# PART2_PowerSupply.net
KiCad netlist of a schematic drawn in Altium Designer
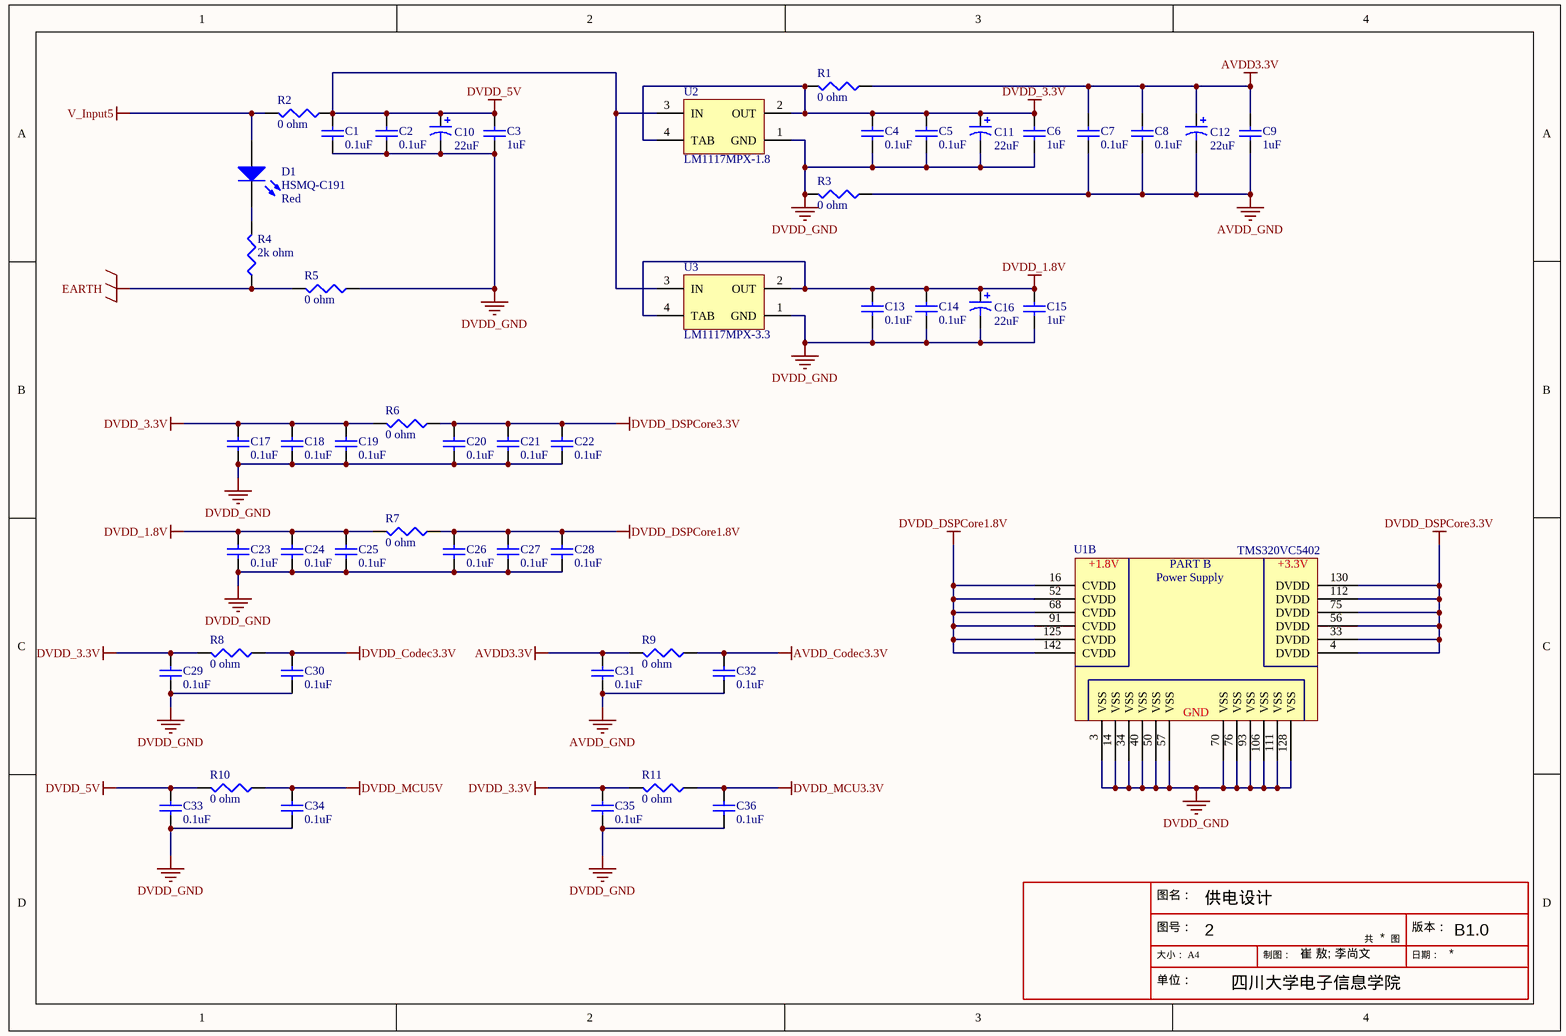
[diagram p0: PART2_PowerSupply.SchDoc]

(export (version "E")
  (design (tool "Eeschema 10.0.6"))
  (components
    (comp (ref "C1")
      (value "0.1uF")
      (footprint "1608[0603]")
      (description "贴片电容 1608")
      (fields (field (name "Comment") "Cap Semi") (field (name "PUBLISHER") "Altium Limited"))
      (libsource (lib "Miscellaneous Devices") (part "Cap Semi"))
    )
    (comp (ref "C2")
      (value "0.1uF")
      (footprint "1608[0603]")
      (description "贴片电容 1608")
      (fields (field (name "Comment") "Cap Semi") (field (name "PUBLISHER") "Altium Limited"))
      (libsource (lib "Miscellaneous Devices") (part "Cap Semi"))
    )
    (comp (ref "C3")
      (value "1uF")
      (footprint "1608[0603]")
      (description "贴片电容 1608")
      (fields (field (name "Comment") "Cap Semi") (field (name "PUBLISHER") "Altium Limited"))
      (libsource (lib "Miscellaneous Devices") (part "Cap Semi"))
    )
    (comp (ref "C4")
      (value "0.1uF")
      (footprint "1608[0603]")
      (description "贴片电容 1608")
      (fields (field (name "Comment") "Cap Semi") (field (name "PUBLISHER") "Altium Limited"))
      (libsource (lib "Miscellaneous Devices") (part "Cap Semi"))
    )
    (comp (ref "C5")
      (value "0.1uF")
      (footprint "1608[0603]")
      (description "贴片电容 1608")
      (fields (field (name "Comment") "Cap Semi") (field (name "PUBLISHER") "Altium Limited"))
      (libsource (lib "Miscellaneous Devices") (part "Cap Semi"))
    )
    (comp (ref "C6")
      (value "1uF")
      (footprint "1608[0603]")
      (description "贴片电容 1608")
      (fields (field (name "Comment") "Cap Semi") (field (name "PUBLISHER") "Altium Limited"))
      (libsource (lib "Miscellaneous Devices") (part "Cap Semi"))
    )
    (comp (ref "C7")
      (value "0.1uF")
      (footprint "1608[0603]")
      (description "贴片电容 1608")
      (fields (field (name "Comment") "Cap Semi") (field (name "PUBLISHER") "Altium Limited"))
      (libsource (lib "Miscellaneous Devices") (part "Cap Semi"))
    )
    (comp (ref "C8")
      (value "0.1uF")
      (footprint "1608[0603]")
      (description "贴片电容 1608")
      (fields (field (name "Comment") "Cap Semi") (field (name "PUBLISHER") "Altium Limited"))
      (libsource (lib "Miscellaneous Devices") (part "Cap Semi"))
    )
    (comp (ref "C9")
      (value "1uF")
      (footprint "1608[0603]")
      (description "贴片电容 1608")
      (fields (field (name "Comment") "Cap Semi") (field (name "PUBLISHER") "Altium Limited"))
      (libsource (lib "Miscellaneous Devices") (part "Cap Semi"))
    )
    (comp (ref "C10")
      (value "22uF")
      (footprint "C0805")
      (description "贴片钽电容 C0805")
      (fields (field (name "Comment") "Cap Tan") (field (name "PUBLISHER") "Altium Limited"))
      (libsource (lib "Miscellaneous Devices") (part "Cap Pol3"))
    )
    (comp (ref "C11")
      (value "22uF")
      (footprint "C0805")
      (description "贴片钽电容 C0805")
      (fields (field (name "Comment") "Cap Tan") (field (name "PUBLISHER") "Altium Limited"))
      (libsource (lib "Miscellaneous Devices") (part "Cap Pol3"))
    )
    (comp (ref "C12")
      (value "22uF")
      (footprint "C0805")
      (description "贴片钽电容 C0805")
      (fields (field (name "Comment") "Cap Tan") (field (name "PUBLISHER") "Altium Limited"))
      (libsource (lib "Miscellaneous Devices") (part "Cap Pol3"))
    )
    (comp (ref "C13")
      (value "0.1uF")
      (footprint "1608[0603]")
      (description "贴片电容 1608")
      (fields (field (name "Comment") "Cap Semi") (field (name "PUBLISHER") "Altium Limited"))
      (libsource (lib "Miscellaneous Devices") (part "Cap Semi"))
    )
    (comp (ref "C14")
      (value "0.1uF")
      (footprint "1608[0603]")
      (description "贴片电容 1608")
      (fields (field (name "Comment") "Cap Semi") (field (name "PUBLISHER") "Altium Limited"))
      (libsource (lib "Miscellaneous Devices") (part "Cap Semi"))
    )
    (comp (ref "C15")
      (value "1uF")
      (footprint "1608[0603]")
      (description "贴片电容 1608")
      (fields (field (name "Comment") "Cap Semi") (field (name "PUBLISHER") "Altium Limited"))
      (libsource (lib "Miscellaneous Devices") (part "Cap Semi"))
    )
    (comp (ref "C16")
      (value "22uF")
      (footprint "C0805")
      (description "贴片钽电容 C0805")
      (fields (field (name "Comment") "Cap Tan") (field (name "PUBLISHER") "Altium Limited"))
      (libsource (lib "Miscellaneous Devices") (part "Cap Pol3"))
    )
    (comp (ref "C17")
      (value "0.1uF")
      (footprint "1608[0603]")
      (description "贴片电容 1608")
      (fields (field (name "Comment") "Cap Semi") (field (name "PUBLISHER") "Altium Limited"))
      (libsource (lib "Miscellaneous Devices") (part "Cap Semi"))
    )
    (comp (ref "C18")
      (value "0.1uF")
      (footprint "1608[0603]")
      (description "贴片电容 1608")
      (fields (field (name "Comment") "Cap Semi") (field (name "PUBLISHER") "Altium Limited"))
      (libsource (lib "Miscellaneous Devices") (part "Cap Semi"))
    )
    (comp (ref "C19")
      (value "0.1uF")
      (footprint "1608[0603]")
      (description "贴片电容 1608")
      (fields (field (name "Comment") "Cap Semi") (field (name "PUBLISHER") "Altium Limited"))
      (libsource (lib "Miscellaneous Devices") (part "Cap Semi"))
    )
    (comp (ref "C20")
      (value "0.1uF")
      (footprint "1608[0603]")
      (description "贴片电容 1608")
      (fields (field (name "Comment") "Cap Semi") (field (name "PUBLISHER") "Altium Limited"))
      (libsource (lib "Miscellaneous Devices") (part "Cap Semi"))
    )
    (comp (ref "C21")
      (value "0.1uF")
      (footprint "1608[0603]")
      (description "贴片电容 1608")
      (fields (field (name "Comment") "Cap Semi") (field (name "PUBLISHER") "Altium Limited"))
      (libsource (lib "Miscellaneous Devices") (part "Cap Semi"))
    )
    (comp (ref "C22")
      (value "0.1uF")
      (footprint "1608[0603]")
      (description "贴片电容 1608")
      (fields (field (name "Comment") "Cap Semi") (field (name "PUBLISHER") "Altium Limited"))
      (libsource (lib "Miscellaneous Devices") (part "Cap Semi"))
    )
    (comp (ref "C23")
      (value "0.1uF")
      (footprint "1608[0603]")
      (description "贴片电容 1608")
      (fields (field (name "Comment") "Cap Semi") (field (name "PUBLISHER") "Altium Limited"))
      (libsource (lib "Miscellaneous Devices") (part "Cap Semi"))
    )
    (comp (ref "C24")
      (value "0.1uF")
      (footprint "1608[0603]")
      (description "贴片电容 1608")
      (fields (field (name "Comment") "Cap Semi") (field (name "PUBLISHER") "Altium Limited"))
      (libsource (lib "Miscellaneous Devices") (part "Cap Semi"))
    )
    (comp (ref "C25")
      (value "0.1uF")
      (footprint "1608[0603]")
      (description "贴片电容 1608")
      (fields (field (name "Comment") "Cap Semi") (field (name "PUBLISHER") "Altium Limited"))
      (libsource (lib "Miscellaneous Devices") (part "Cap Semi"))
    )
    (comp (ref "C26")
      (value "0.1uF")
      (footprint "1608[0603]")
      (description "贴片电容 1608")
      (fields (field (name "Comment") "Cap Semi") (field (name "PUBLISHER") "Altium Limited"))
      (libsource (lib "Miscellaneous Devices") (part "Cap Semi"))
    )
    (comp (ref "C27")
      (value "0.1uF")
      (footprint "1608[0603]")
      (description "贴片电容 1608")
      (fields (field (name "Comment") "Cap Semi") (field (name "PUBLISHER") "Altium Limited"))
      (libsource (lib "Miscellaneous Devices") (part "Cap Semi"))
    )
    (comp (ref "C28")
      (value "0.1uF")
      (footprint "1608[0603]")
      (description "贴片电容 1608")
      (fields (field (name "Comment") "Cap Semi") (field (name "PUBLISHER") "Altium Limited"))
      (libsource (lib "Miscellaneous Devices") (part "Cap Semi"))
    )
    (comp (ref "C29")
      (value "0.1uF")
      (footprint "1608[0603]")
      (description "贴片电容 1608")
      (fields (field (name "Comment") "Cap Semi") (field (name "PUBLISHER") "Altium Limited"))
      (libsource (lib "Miscellaneous Devices") (part "Cap Semi"))
    )
    (comp (ref "C30")
      (value "0.1uF")
      (footprint "1608[0603]")
      (description "贴片电容 1608")
      (fields (field (name "Comment") "Cap Semi") (field (name "PUBLISHER") "Altium Limited"))
      (libsource (lib "Miscellaneous Devices") (part "Cap Semi"))
    )
    (comp (ref "C31")
      (value "0.1uF")
      (footprint "1608[0603]")
      (description "贴片电容 1608")
      (fields (field (name "Comment") "Cap Semi") (field (name "PUBLISHER") "Altium Limited"))
      (libsource (lib "Miscellaneous Devices") (part "Cap Semi"))
    )
    (comp (ref "C32")
      (value "0.1uF")
      (footprint "1608[0603]")
      (description "贴片电容 1608")
      (fields (field (name "Comment") "Cap Semi") (field (name "PUBLISHER") "Altium Limited"))
      (libsource (lib "Miscellaneous Devices") (part "Cap Semi"))
    )
    (comp (ref "C33")
      (value "0.1uF")
      (footprint "1608[0603]")
      (description "贴片电容 1608")
      (fields (field (name "Comment") "Cap Semi") (field (name "PUBLISHER") "Altium Limited"))
      (libsource (lib "Miscellaneous Devices") (part "Cap Semi"))
    )
    (comp (ref "C34")
      (value "0.1uF")
      (footprint "1608[0603]")
      (description "贴片电容 1608")
      (fields (field (name "Comment") "Cap Semi") (field (name "PUBLISHER") "Altium Limited"))
      (libsource (lib "Miscellaneous Devices") (part "Cap Semi"))
    )
    (comp (ref "C35")
      (value "0.1uF")
      (footprint "1608[0603]")
      (description "贴片电容 1608")
      (fields (field (name "Comment") "Cap Semi") (field (name "PUBLISHER") "Altium Limited"))
      (libsource (lib "Miscellaneous Devices") (part "Cap Semi"))
    )
    (comp (ref "C36")
      (value "0.1uF")
      (footprint "1608[0603]")
      (description "贴片电容 1608")
      (fields (field (name "Comment") "Cap Semi") (field (name "PUBLISHER") "Altium Limited"))
      (libsource (lib "Miscellaneous Devices") (part "Cap Semi"))
    )
    (comp (ref "D1")
      (value "HSMQ-C191")
      (footprint "1.6X0.8X0.6")
      (description "Top Mount Low Profile Chip LED, Green")
      (fields (field (name "LED_COLOUR") "Red") (field (name "PUBLISHER") "Altium Limited"))
      (libsource (lib "Agilent Optoelectronic LED") (part "HSMQ-C191"))
    )
    (comp (ref "R1")
      (value "0 ohm")
      (footprint "J1-0603")
      (description "贴片电阻 0603")
      (fields (field (name "Comment") "Res3") (field (name "PUBLISHER") "Altium Limited"))
      (libsource (lib "Miscellaneous Devices") (part "Res3"))
    )
    (comp (ref "R2")
      (value "0 ohm")
      (footprint "J1-0603")
      (description "贴片电阻 0603")
      (fields (field (name "Comment") "Res3") (field (name "PUBLISHER") "Altium Limited"))
      (libsource (lib "Miscellaneous Devices") (part "Res3"))
    )
    (comp (ref "R3")
      (value "0 ohm")
      (footprint "J1-0603")
      (description "贴片电阻 0603")
      (fields (field (name "Comment") "Res3") (field (name "PUBLISHER") "Altium Limited"))
      (libsource (lib "Miscellaneous Devices") (part "Res3"))
    )
    (comp (ref "R4")
      (value "2k ohm")
      (footprint "J1-0603")
      (description "贴片电阻 0603")
      (fields (field (name "Comment") "Res3") (field (name "PUBLISHER") "Altium Limited"))
      (libsource (lib "Miscellaneous Devices") (part "Res3"))
    )
    (comp (ref "R5")
      (value "0 ohm")
      (footprint "J1-0603")
      (description "贴片电阻 0603")
      (fields (field (name "Comment") "Res3") (field (name "PUBLISHER") "Altium Limited"))
      (libsource (lib "Miscellaneous Devices") (part "Res3"))
    )
    (comp (ref "R6")
      (value "0 ohm")
      (footprint "J1-0603")
      (description "贴片电阻 0603")
      (fields (field (name "Comment") "Res3") (field (name "PUBLISHER") "Altium Limited"))
      (libsource (lib "Miscellaneous Devices") (part "Res3"))
    )
    (comp (ref "R7")
      (value "0 ohm")
      (footprint "J1-0603")
      (description "贴片电阻 0603")
      (fields (field (name "Comment") "Res3") (field (name "PUBLISHER") "Altium Limited"))
      (libsource (lib "Miscellaneous Devices") (part "Res3"))
    )
    (comp (ref "R8")
      (value "0 ohm")
      (footprint "J1-0603")
      (description "贴片电阻 0603")
      (fields (field (name "Comment") "Res3") (field (name "PUBLISHER") "Altium Limited"))
      (libsource (lib "Miscellaneous Devices") (part "Res3"))
    )
    (comp (ref "R9")
      (value "0 ohm")
      (footprint "J1-0603")
      (description "贴片电阻 0603")
      (fields (field (name "Comment") "Res3") (field (name "PUBLISHER") "Altium Limited"))
      (libsource (lib "Miscellaneous Devices") (part "Res3"))
    )
    (comp (ref "R10")
      (value "0 ohm")
      (footprint "J1-0603")
      (description "贴片电阻 0603")
      (fields (field (name "Comment") "Res3") (field (name "PUBLISHER") "Altium Limited"))
      (libsource (lib "Miscellaneous Devices") (part "Res3"))
    )
    (comp (ref "R11")
      (value "0 ohm")
      (footprint "J1-0603")
      (description "贴片电阻 0603")
      (fields (field (name "Comment") "Res3") (field (name "PUBLISHER") "Altium Limited"))
      (libsource (lib "Miscellaneous Devices") (part "Res3"))
    )
    (comp (ref "U1")
      (value "TMS320VC5402")
      (footprint "TMS320VC5401_PQFP144")
      (libsource (lib "TMS320VC5401") (part "TMS320VC5402"))
    )
    (comp (ref "U2")
      (value "LM1117MPX-1.8")
      (footprint "MP04A_N")
      (description "800mA Low-Dropout Linear Regulator, 4-pin SOT-223")
      (fields
        (field (name "MANUFACTURER") "National Semiconductor")
        (field (name "PUBLISHER") "Altium Limited")
      )
      (libsource (lib "NSC LDO") (part "LM1117MPX-1.8"))
    )
    (comp (ref "U3")
      (value "LM1117MPX-3.3")
      (footprint "MP04A_N")
      (description "800mA Low-Dropout Linear Regulator, 4-pin SOT-223")
      (fields
        (field (name "MANUFACTURER") "National Semiconductor")
        (field (name "PUBLISHER") "Altium Limited")
      )
      (libsource (lib "NSC LDO") (part "LM1117MPX-3.3"))
    )
  )
  (nets
    (net (code "1") (name "AVDD3.3V") (class "Default")
      (node (ref "C12") (pin "1") (pinfunction "1_1") (pintype "passive"))
      (node (ref "C31") (pin "1") (pinfunction "1_1") (pintype "passive"))
      (node (ref "C7") (pin "1") (pinfunction "1_1") (pintype "passive"))
      (node (ref "C8") (pin "1") (pinfunction "1_1") (pintype "passive"))
      (node (ref "C9") (pin "1") (pinfunction "1_1") (pintype "passive"))
      (node (ref "R1") (pin "1") (pinfunction "1_1") (pintype "passive"))
      (node (ref "R9") (pin "2") (pinfunction "2_2") (pintype "passive"))
    )
    (net (code "2") (name "AVDD_Codec3.3V") (class "Default")
      (node (ref "C32") (pin "1") (pinfunction "1_1") (pintype "passive"))
      (node (ref "R9") (pin "1") (pinfunction "1_1") (pintype "passive"))
    )
    (net (code "3") (name "AVDD_GND") (class "Default")
      (node (ref "C12") (pin "2") (pinfunction "2_2") (pintype "passive"))
      (node (ref "C31") (pin "2") (pinfunction "2_2") (pintype "passive"))
      (node (ref "C32") (pin "2") (pinfunction "2_2") (pintype "passive"))
      (node (ref "C7") (pin "2") (pinfunction "2_2") (pintype "passive"))
      (node (ref "C8") (pin "2") (pinfunction "2_2") (pintype "passive"))
      (node (ref "C9") (pin "2") (pinfunction "2_2") (pintype "passive"))
      (node (ref "R3") (pin "1") (pinfunction "1_1") (pintype "passive"))
    )
    (net (code "4") (name "DVDD_1.8V") (class "Default")
      (node (ref "C13") (pin "1") (pinfunction "1_1") (pintype "passive"))
      (node (ref "C14") (pin "1") (pinfunction "1_1") (pintype "passive"))
      (node (ref "C15") (pin "1") (pinfunction "1_1") (pintype "passive"))
      (node (ref "C16") (pin "1") (pinfunction "1_1") (pintype "passive"))
      (node (ref "C23") (pin "1") (pinfunction "1_1") (pintype "passive"))
      (node (ref "C24") (pin "1") (pinfunction "1_1") (pintype "passive"))
      (node (ref "C25") (pin "1") (pinfunction "1_1") (pintype "passive"))
      (node (ref "R7") (pin "2") (pinfunction "2_2") (pintype "passive"))
      (node (ref "U3") (pin "2") (pinfunction "OUT_2") (pintype "power_in"))
      (node (ref "U3") (pin "4") (pinfunction "TAB_4") (pintype "power_in"))
    )
    (net (code "5") (name "DVDD_3.3V") (class "Default")
      (node (ref "C11") (pin "1") (pinfunction "1_1") (pintype "passive"))
      (node (ref "C17") (pin "1") (pinfunction "1_1") (pintype "passive"))
      (node (ref "C18") (pin "1") (pinfunction "1_1") (pintype "passive"))
      (node (ref "C19") (pin "1") (pinfunction "1_1") (pintype "passive"))
      (node (ref "C29") (pin "1") (pinfunction "1_1") (pintype "passive"))
      (node (ref "C35") (pin "1") (pinfunction "1_1") (pintype "passive"))
      (node (ref "C4") (pin "1") (pinfunction "1_1") (pintype "passive"))
      (node (ref "C5") (pin "1") (pinfunction "1_1") (pintype "passive"))
      (node (ref "C6") (pin "1") (pinfunction "1_1") (pintype "passive"))
      (node (ref "R1") (pin "2") (pinfunction "2_2") (pintype "passive"))
      (node (ref "R11") (pin "2") (pinfunction "2_2") (pintype "passive"))
      (node (ref "R6") (pin "2") (pinfunction "2_2") (pintype "passive"))
      (node (ref "R8") (pin "2") (pinfunction "2_2") (pintype "passive"))
      (node (ref "U2") (pin "2") (pinfunction "OUT_2") (pintype "power_in"))
      (node (ref "U2") (pin "4") (pinfunction "TAB_4") (pintype "power_in"))
    )
    (net (code "6") (name "DVDD_5V") (class "Default")
      (node (ref "C1") (pin "1") (pinfunction "1_1") (pintype "passive"))
      (node (ref "C10") (pin "1") (pinfunction "1_1") (pintype "passive"))
      (node (ref "C2") (pin "1") (pinfunction "1_1") (pintype "passive"))
      (node (ref "C3") (pin "1") (pinfunction "1_1") (pintype "passive"))
      (node (ref "C33") (pin "1") (pinfunction "1_1") (pintype "passive"))
      (node (ref "R10") (pin "2") (pinfunction "2_2") (pintype "passive"))
      (node (ref "R2") (pin "1") (pinfunction "1_1") (pintype "passive"))
      (node (ref "U2") (pin "3") (pinfunction "IN_3") (pintype "power_in"))
      (node (ref "U3") (pin "3") (pinfunction "IN_3") (pintype "power_in"))
    )
    (net (code "7") (name "DVDD_Codec3.3V") (class "Default")
      (node (ref "C30") (pin "1") (pinfunction "1_1") (pintype "passive"))
      (node (ref "R8") (pin "1") (pinfunction "1_1") (pintype "passive"))
    )
    (net (code "8") (name "DVDD_DSPCore1.8V") (class "Default")
      (node (ref "C26") (pin "1") (pinfunction "1_1") (pintype "passive"))
      (node (ref "C27") (pin "1") (pinfunction "1_1") (pintype "passive"))
      (node (ref "C28") (pin "1") (pinfunction "1_1") (pintype "passive"))
      (node (ref "R7") (pin "1") (pinfunction "1_1") (pintype "passive"))
      (node (ref "U1") (pin "125") (pinfunction "CVDD_125") (pintype "power_in"))
      (node (ref "U1") (pin "142") (pinfunction "CVDD_142") (pintype "power_in"))
      (node (ref "U1") (pin "16") (pinfunction "CVDD_16") (pintype "power_in"))
      (node (ref "U1") (pin "52") (pinfunction "CVDD_52") (pintype "power_in"))
      (node (ref "U1") (pin "68") (pinfunction "CVDD_68") (pintype "power_in"))
      (node (ref "U1") (pin "91") (pinfunction "CVDD_91") (pintype "power_in"))
    )
    (net (code "9") (name "DVDD_DSPCore3.3V") (class "Default")
      (node (ref "C20") (pin "1") (pinfunction "1_1") (pintype "passive"))
      (node (ref "C21") (pin "1") (pinfunction "1_1") (pintype "passive"))
      (node (ref "C22") (pin "1") (pinfunction "1_1") (pintype "passive"))
      (node (ref "R6") (pin "1") (pinfunction "1_1") (pintype "passive"))
      (node (ref "U1") (pin "112") (pinfunction "DVDD_112") (pintype "power_in"))
      (node (ref "U1") (pin "130") (pinfunction "DVDD_130") (pintype "power_in"))
      (node (ref "U1") (pin "33") (pinfunction "DVDD_33") (pintype "power_in"))
      (node (ref "U1") (pin "4") (pinfunction "DVDD_4") (pintype "power_in"))
      (node (ref "U1") (pin "56") (pinfunction "DVDD_56") (pintype "power_in"))
      (node (ref "U1") (pin "75") (pinfunction "DVDD_75") (pintype "power_in"))
    )
    (net (code "10") (name "DVDD_GND") (class "Default")
      (node (ref "C1") (pin "2") (pinfunction "2_2") (pintype "passive"))
      (node (ref "C10") (pin "2") (pinfunction "2_2") (pintype "passive"))
      (node (ref "C11") (pin "2") (pinfunction "2_2") (pintype "passive"))
      (node (ref "C13") (pin "2") (pinfunction "2_2") (pintype "passive"))
      (node (ref "C14") (pin "2") (pinfunction "2_2") (pintype "passive"))
      (node (ref "C15") (pin "2") (pinfunction "2_2") (pintype "passive"))
      (node (ref "C16") (pin "2") (pinfunction "2_2") (pintype "passive"))
      (node (ref "C17") (pin "2") (pinfunction "2_2") (pintype "passive"))
      (node (ref "C18") (pin "2") (pinfunction "2_2") (pintype "passive"))
      (node (ref "C19") (pin "2") (pinfunction "2_2") (pintype "passive"))
      (node (ref "C2") (pin "2") (pinfunction "2_2") (pintype "passive"))
      (node (ref "C20") (pin "2") (pinfunction "2_2") (pintype "passive"))
      (node (ref "C21") (pin "2") (pinfunction "2_2") (pintype "passive"))
      (node (ref "C22") (pin "2") (pinfunction "2_2") (pintype "passive"))
      (node (ref "C23") (pin "2") (pinfunction "2_2") (pintype "passive"))
      (node (ref "C24") (pin "2") (pinfunction "2_2") (pintype "passive"))
      (node (ref "C25") (pin "2") (pinfunction "2_2") (pintype "passive"))
      (node (ref "C26") (pin "2") (pinfunction "2_2") (pintype "passive"))
      (node (ref "C27") (pin "2") (pinfunction "2_2") (pintype "passive"))
      (node (ref "C28") (pin "2") (pinfunction "2_2") (pintype "passive"))
      (node (ref "C29") (pin "2") (pinfunction "2_2") (pintype "passive"))
      (node (ref "C3") (pin "2") (pinfunction "2_2") (pintype "passive"))
      (node (ref "C30") (pin "2") (pinfunction "2_2") (pintype "passive"))
      (node (ref "C33") (pin "2") (pinfunction "2_2") (pintype "passive"))
      (node (ref "C34") (pin "2") (pinfunction "2_2") (pintype "passive"))
      (node (ref "C35") (pin "2") (pinfunction "2_2") (pintype "passive"))
      (node (ref "C36") (pin "2") (pinfunction "2_2") (pintype "passive"))
      (node (ref "C4") (pin "2") (pinfunction "2_2") (pintype "passive"))
      (node (ref "C5") (pin "2") (pinfunction "2_2") (pintype "passive"))
      (node (ref "C6") (pin "2") (pinfunction "2_2") (pintype "passive"))
      (node (ref "R3") (pin "2") (pinfunction "2_2") (pintype "passive"))
      (node (ref "R5") (pin "1") (pinfunction "1_1") (pintype "passive"))
      (node (ref "U1") (pin "106") (pinfunction "VSS_106") (pintype "power_in"))
      (node (ref "U1") (pin "111") (pinfunction "VSS_111") (pintype "power_in"))
      (node (ref "U1") (pin "128") (pinfunction "VSS_128") (pintype "power_in"))
      (node (ref "U1") (pin "14") (pinfunction "VSS_14") (pintype "power_in"))
      (node (ref "U1") (pin "3") (pinfunction "VSS_3") (pintype "power_in"))
      (node (ref "U1") (pin "34") (pinfunction "VSS_34") (pintype "power_in"))
      (node (ref "U1") (pin "40") (pinfunction "VSS_40") (pintype "power_in"))
      (node (ref "U1") (pin "50") (pinfunction "VSS_50") (pintype "power_in"))
      (node (ref "U1") (pin "57") (pinfunction "VSS_57") (pintype "power_in"))
      (node (ref "U1") (pin "70") (pinfunction "VSS_70") (pintype "power_in"))
      (node (ref "U1") (pin "76") (pinfunction "VSS_76") (pintype "power_in"))
      (node (ref "U1") (pin "93") (pinfunction "VSS_93") (pintype "power_in"))
      (node (ref "U2") (pin "1") (pinfunction "GND_1") (pintype "power_in"))
      (node (ref "U3") (pin "1") (pinfunction "GND_1") (pintype "power_in"))
    )
    (net (code "11") (name "DVDD_MCU3.3V") (class "Default")
      (node (ref "C36") (pin "1") (pinfunction "1_1") (pintype "passive"))
      (node (ref "R11") (pin "1") (pinfunction "1_1") (pintype "passive"))
    )
    (net (code "12") (name "DVDD_MCU5V") (class "Default")
      (node (ref "C34") (pin "1") (pinfunction "1_1") (pintype "passive"))
      (node (ref "R10") (pin "1") (pinfunction "1_1") (pintype "passive"))
    )
    (net (code "13") (name "EARTH") (class "Default")
      (node (ref "R4") (pin "1") (pinfunction "1_1") (pintype "passive"))
      (node (ref "R5") (pin "2") (pinfunction "2_2") (pintype "passive"))
    )
    (net (code "14") (name "Net-(D1-K)") (class "Default")
      (node (ref "D1") (pin "2") (pinfunction "K_2") (pintype "passive"))
      (node (ref "R4") (pin "2") (pinfunction "2_2") (pintype "passive"))
    )
    (net (code "15") (name "V_Input5") (class "Default")
      (node (ref "D1") (pin "1") (pinfunction "A_1") (pintype "passive"))
      (node (ref "R2") (pin "2") (pinfunction "2_2") (pintype "passive"))
    )
  )
)
